# MCP9808T.net
KiCad netlist of a schematic drawn in Altium Designer
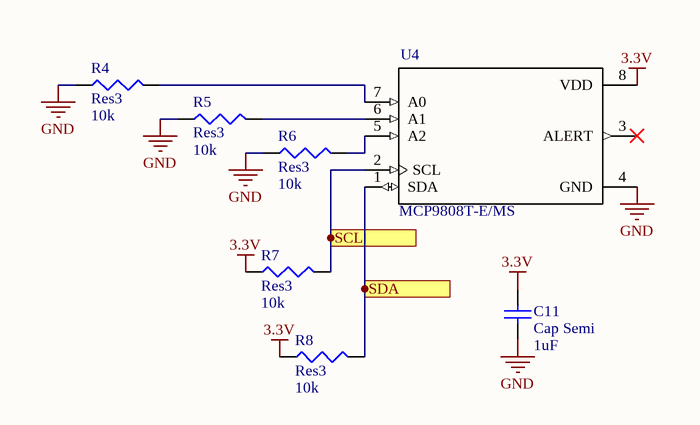
[diagram p0: MCP9808T.SchDoc]

(export (version "E")
  (design (tool "Eeschema 10.0.6"))
  (components
    (comp (ref "C11")
      (value "Cap Semi")
      (footprint "C1206")
      (description "Capacitor (Semiconductor SIM Model)")
      (fields (field (name "ALTIUM_VALUE") "1uF") (field (name "PUBLISHER") "Altium Limited"))
      (libsource (lib "Miscellaneous Devices") (part "Cap Semi"))
    )
    (comp (ref "R4")
      (value "Res3")
      (footprint "6-0805_L")
      (description "Resistor")
      (fields (field (name "ALTIUM_VALUE") "10k") (field (name "PUBLISHER") "Altium Limited"))
      (libsource (lib "Miscellaneous Devices") (part "Res3"))
    )
    (comp (ref "R5")
      (value "Res3")
      (footprint "6-0805_L")
      (description "Resistor")
      (fields (field (name "ALTIUM_VALUE") "10k") (field (name "PUBLISHER") "Altium Limited"))
      (libsource (lib "Miscellaneous Devices") (part "Res3"))
    )
    (comp (ref "R6")
      (value "Res3")
      (footprint "6-0805_L")
      (description "Resistor")
      (fields (field (name "ALTIUM_VALUE") "10k") (field (name "PUBLISHER") "Altium Limited"))
      (libsource (lib "Miscellaneous Devices") (part "Res3"))
    )
    (comp (ref "R7")
      (value "Res3")
      (footprint "6-0805_L")
      (description "Resistor")
      (fields (field (name "ALTIUM_VALUE") "10k") (field (name "PUBLISHER") "Altium Limited"))
      (libsource (lib "Miscellaneous Devices") (part "Res3"))
    )
    (comp (ref "R8")
      (value "Res3")
      (footprint "6-0805_L")
      (description "Resistor")
      (fields (field (name "ALTIUM_VALUE") "10k") (field (name "PUBLISHER") "Altium Limited"))
      (libsource (lib "Miscellaneous Devices") (part "Res3"))
    )
    (comp (ref "U4")
      (value "MCP9808T-E/MS")
      (footprint "*SOP65P490X110-8N")
      (description "MCP9808 Series 3.6 V Memory Module Digital Temperature Sensor SMT - MSOP-8")
      (fields (field (name "MF") "Microchip"))
      (libsource (lib "MCP9808T-E_MS") (part "MCP9808T-E/MS"))
    )
  )
  (nets
    (net (code "1") (name "/SCL") (class "Default")
      (node (ref "R7") (pin "2") (pinfunction "2_2") (pintype "passive"))
      (node (ref "U4") (pin "2") (pinfunction "SCL_2") (pintype "input"))
    )
    (net (code "2") (name "/SDA") (class "Default")
      (node (ref "R8") (pin "2") (pinfunction "2_2") (pintype "passive"))
      (node (ref "U4") (pin "1") (pinfunction "SDA_1") (pintype "bidirectional"))
    )
    (net (code "3") (name "3.3V") (class "Default")
      (node (ref "C11") (pin "2") (pinfunction "2_2") (pintype "passive"))
      (node (ref "R7") (pin "1") (pinfunction "1_1") (pintype "passive"))
      (node (ref "R8") (pin "1") (pinfunction "1_1") (pintype "passive"))
      (node (ref "U4") (pin "8") (pinfunction "VDD_8") (pintype "power_in"))
    )
    (net (code "4") (name "GND") (class "Default")
      (node (ref "C11") (pin "1") (pinfunction "1_1") (pintype "passive"))
      (node (ref "R4") (pin "1") (pinfunction "1_1") (pintype "passive"))
      (node (ref "R5") (pin "1") (pinfunction "1_1") (pintype "passive"))
      (node (ref "R6") (pin "1") (pinfunction "1_1") (pintype "passive"))
      (node (ref "U4") (pin "4") (pinfunction "GND_4") (pintype "power_in"))
    )
    (net (code "5") (name "Net-(U4-A0)") (class "Default")
      (node (ref "R4") (pin "2") (pinfunction "2_2") (pintype "passive"))
      (node (ref "U4") (pin "7") (pinfunction "A0_7") (pintype "input"))
    )
    (net (code "6") (name "Net-(U4-A1)") (class "Default")
      (node (ref "R5") (pin "2") (pinfunction "2_2") (pintype "passive"))
      (node (ref "U4") (pin "6") (pinfunction "A1_6") (pintype "input"))
    )
    (net (code "7") (name "Net-(U4-A2)") (class "Default")
      (node (ref "R6") (pin "2") (pinfunction "2_2") (pintype "passive"))
      (node (ref "U4") (pin "5") (pinfunction "A2_5") (pintype "input"))
    )
    (net (code "8") (name "unconnected-(U4-ALERT-Pad3)") (class "Default")
      (node (ref "U4") (pin "3") (pinfunction "ALERT_3") (pintype "output+no_connect"))
    )
  )
)
